# IntrepidDashboard.net
KiCad netlist of a schematic drawn in EAGLE
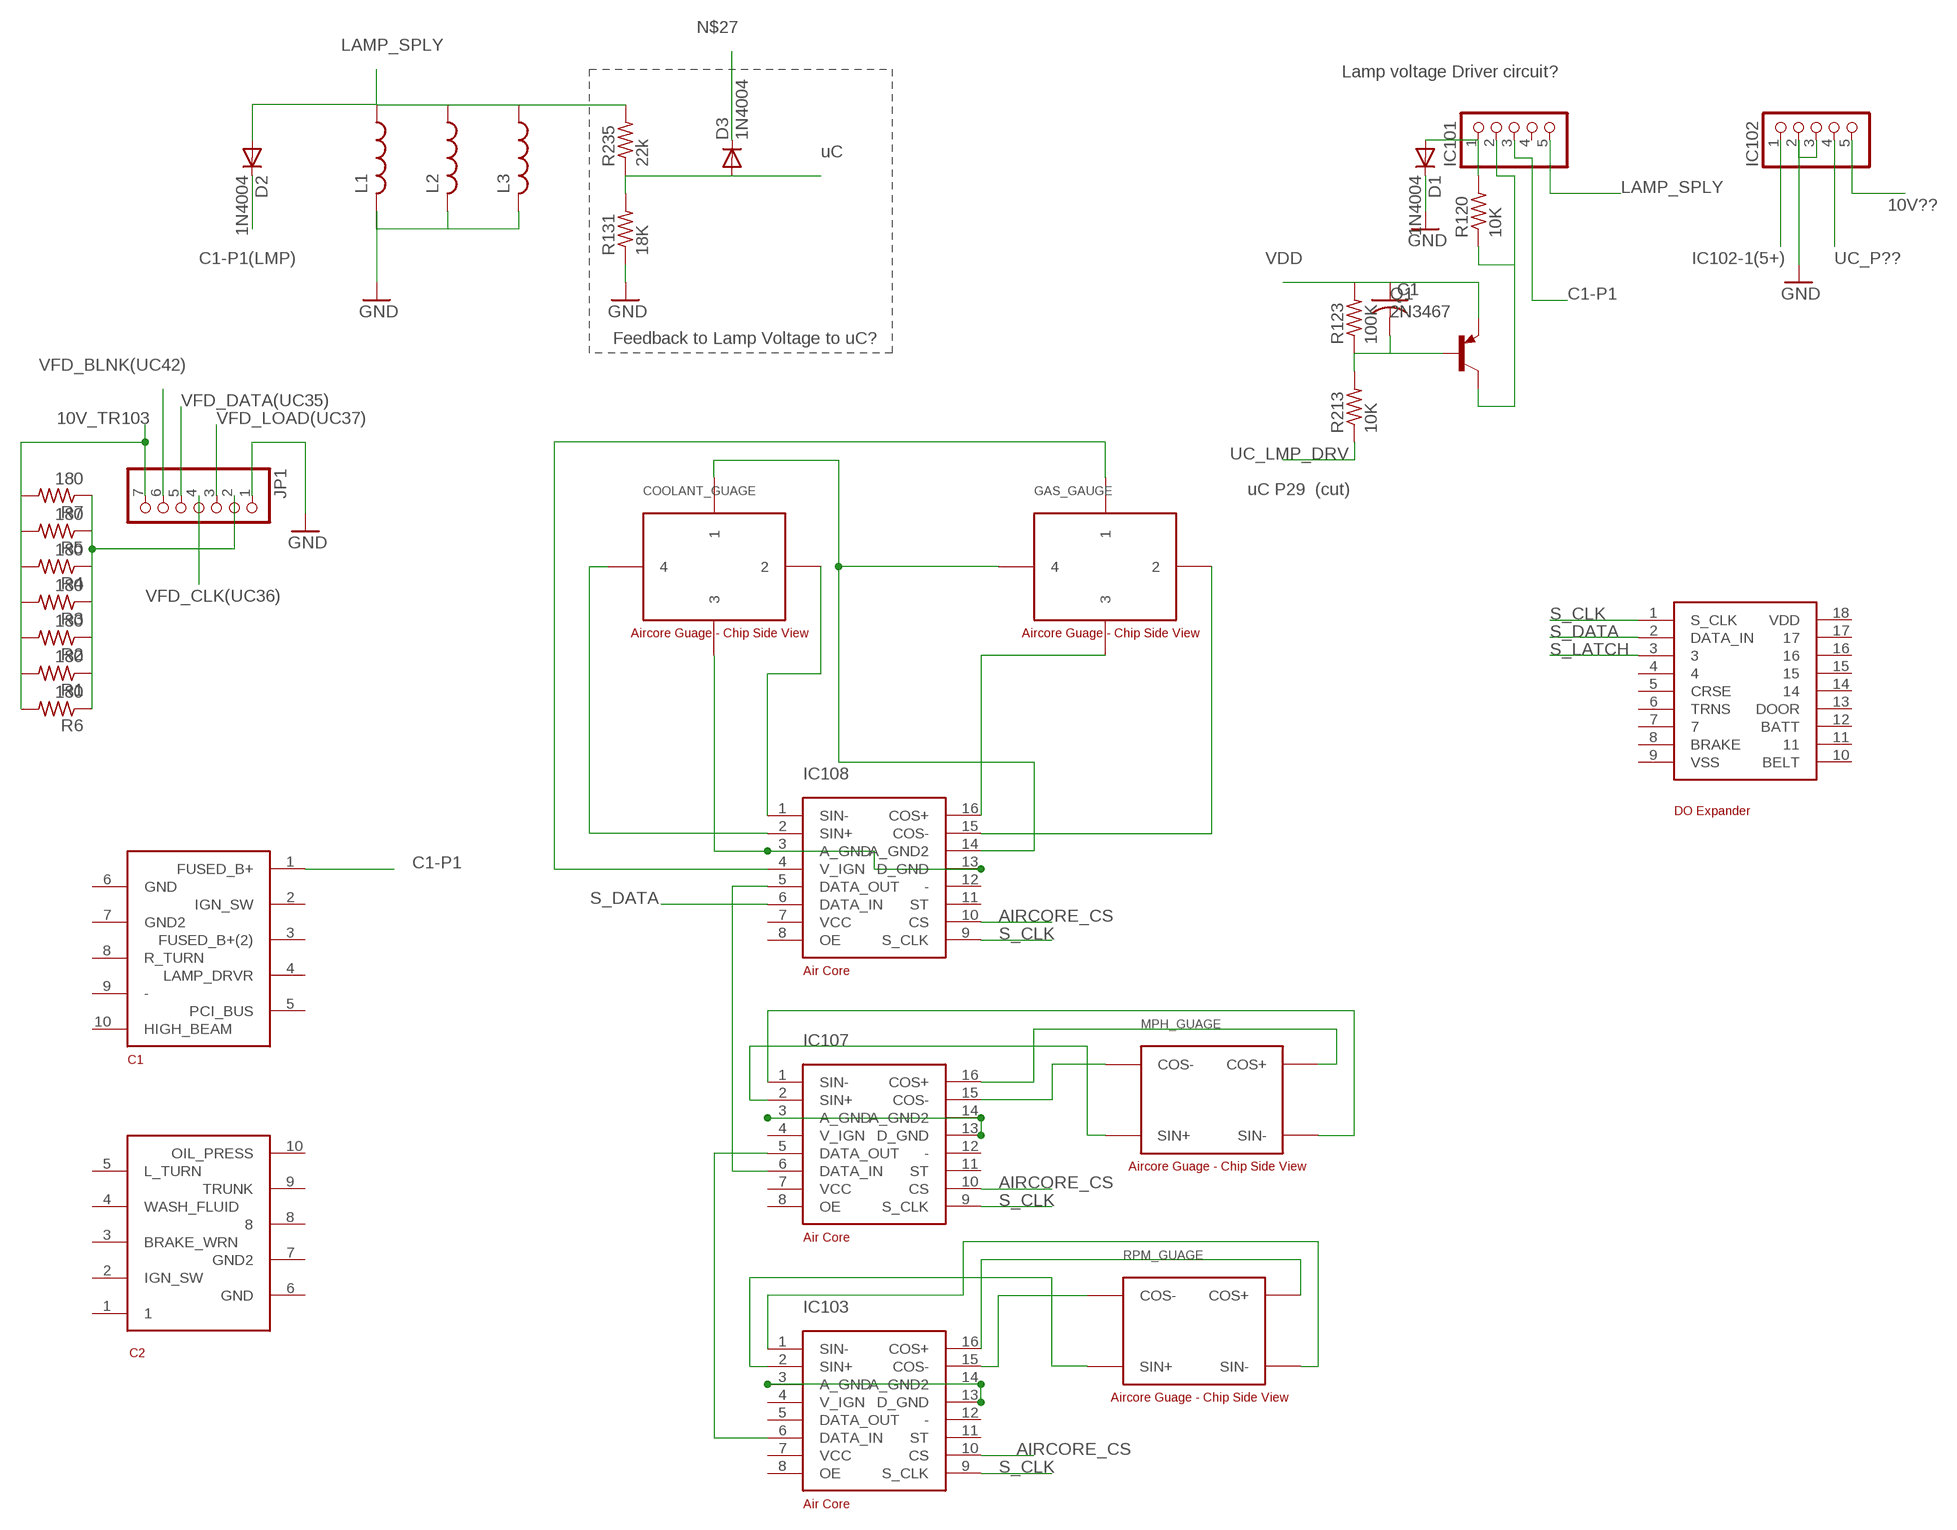
[diagram p0: schematic, sheet 1]

(export (version "E")
  (design (tool "Eeschema 10.0.6"))
  (components
    (comp (ref "C1")
      (value "C-US025-024X044")
      (footprint "eagle-import:C025-024X044")
      (libsource (lib "eagle-import") (part "C-US025-024X044"))
    )
    (comp (ref "COOLANT_GUAGE")
      (value "AIRCORE_GAUGE1")
      (footprint "eagle-import:AIRCORE1")
      (libsource (lib "eagle-import") (part "AIRCORE_GAUGE1"))
    )
    (comp (ref "D1")
      (value "1N4004")
      (footprint "eagle-import:DO41-10")
      (libsource (lib "eagle-import") (part "1N4004"))
    )
    (comp (ref "D2")
      (value "1N4004")
      (footprint "eagle-import:DO41-10")
      (libsource (lib "eagle-import") (part "1N4004"))
    )
    (comp (ref "D3")
      (value "1N4004")
      (footprint "eagle-import:DO41-10")
      (libsource (lib "eagle-import") (part "1N4004"))
    )
    (comp (ref "GAS_GAUGE")
      (value "AIRCORE_GAUGE1")
      (footprint "eagle-import:AIRCORE1")
      (libsource (lib "eagle-import") (part "AIRCORE_GAUGE1"))
    )
    (comp (ref "IC101")
      (value "PINHD-1X5")
      (footprint "eagle-import:1X05")
      (libsource (lib "eagle-import") (part "PINHD-1X5"))
    )
    (comp (ref "IC102")
      (value "PINHD-1X5")
      (footprint "eagle-import:1X05")
      (libsource (lib "eagle-import") (part "PINHD-1X5"))
    )
    (comp (ref "IC103")
      (value "AIR_CORE")
      (footprint "eagle-import:SOIC-16")
      (libsource (lib "eagle-import") (part "AIR_CORE"))
    )
    (comp (ref "IC107")
      (value "AIR_CORE")
      (footprint "eagle-import:SOIC-16")
      (libsource (lib "eagle-import") (part "AIR_CORE"))
    )
    (comp (ref "IC108")
      (value "AIR_CORE")
      (footprint "eagle-import:SOIC-16")
      (libsource (lib "eagle-import") (part "AIR_CORE"))
    )
    (comp (ref "JP1")
      (value "PINHD-1X7")
      (footprint "eagle-import:1X07")
      (libsource (lib "eagle-import") (part "PINHD-1X7"))
    )
    (comp (ref "L1")
      (value "L-US0204/5")
      (footprint "eagle-import:0204_5")
      (libsource (lib "eagle-import") (part "L-US0204/5"))
    )
    (comp (ref "L2")
      (value "L-US0204/5")
      (footprint "eagle-import:0204_5")
      (libsource (lib "eagle-import") (part "L-US0204/5"))
    )
    (comp (ref "L3")
      (value "L-US0204/5")
      (footprint "eagle-import:0204_5")
      (libsource (lib "eagle-import") (part "L-US0204/5"))
    )
    (comp (ref "MPH_GUAGE")
      (value "AIRCORE_GUAGE2")
      (footprint "eagle-import:AIRCORE1")
      (libsource (lib "eagle-import") (part "AIRCORE_GUAGE2"))
    )
    (comp (ref "Q1")
      (value "2N3467")
      (footprint "eagle-import:TO39")
      (libsource (lib "eagle-import") (part "2N3467"))
    )
    (comp (ref "R1")
      (value "180")
      (footprint "eagle-import:0204V")
      (libsource (lib "eagle-import") (part "R-US_0204/2V"))
    )
    (comp (ref "R2")
      (value "180")
      (footprint "eagle-import:0204V")
      (libsource (lib "eagle-import") (part "R-US_0204/2V"))
    )
    (comp (ref "R3")
      (value "180")
      (footprint "eagle-import:0204V")
      (libsource (lib "eagle-import") (part "R-US_0204/2V"))
    )
    (comp (ref "R4")
      (value "180")
      (footprint "eagle-import:0204V")
      (libsource (lib "eagle-import") (part "R-US_0204/2V"))
    )
    (comp (ref "R5")
      (value "180")
      (footprint "eagle-import:0204V")
      (libsource (lib "eagle-import") (part "R-US_0204/2V"))
    )
    (comp (ref "R6")
      (value "180")
      (footprint "eagle-import:0204V")
      (libsource (lib "eagle-import") (part "R-US_0204/2V"))
    )
    (comp (ref "R7")
      (value "180")
      (footprint "eagle-import:0204V")
      (libsource (lib "eagle-import") (part "R-US_0204/2V"))
    )
    (comp (ref "R120")
      (value "10K")
      (footprint "eagle-import:0204V")
      (libsource (lib "eagle-import") (part "R-US_0204/2V"))
    )
    (comp (ref "R123")
      (value "100K")
      (footprint "eagle-import:0204V")
      (libsource (lib "eagle-import") (part "R-US_0204/2V"))
    )
    (comp (ref "R131")
      (value "18K")
      (footprint "eagle-import:0204V")
      (libsource (lib "eagle-import") (part "R-US_0204/2V"))
    )
    (comp (ref "R213")
      (value "10K")
      (footprint "eagle-import:0204V")
      (libsource (lib "eagle-import") (part "R-US_0204/2V"))
    )
    (comp (ref "R235")
      (value "22k")
      (footprint "eagle-import:0204V")
      (libsource (lib "eagle-import") (part "R-US_0204/2V"))
    )
    (comp (ref "RPM_GUAGE")
      (value "AIRCORE_GUAGE2")
      (footprint "eagle-import:AIRCORE1")
      (libsource (lib "eagle-import") (part "AIRCORE_GUAGE2"))
    )
    (comp (ref "U$1")
      (value "DO_EXPANDER")
      (footprint "eagle-import:SOIC-18")
      (libsource (lib "eagle-import") (part "DO_EXPANDER"))
    )
    (comp (ref "U$2")
      (value "C1")
      (footprint "eagle-import:UMAX_10")
      (libsource (lib "eagle-import") (part "C1"))
    )
    (comp (ref "U$3")
      (value "C2")
      (footprint "eagle-import:UMAX_10")
      (libsource (lib "eagle-import") (part "C2"))
    )
  )
  (nets
    (net (code "1") (name "/10V??") (class "Default")
      (node (ref "IC102") (pin "5") (pinfunction "5_5") (pintype "passive"))
    )
    (net (code "2") (name "/10V_TR103") (class "Default")
      (node (ref "JP1") (pin "7") (pinfunction "7_7") (pintype "passive"))
      (node (ref "R1") (pin "2") (pinfunction "2_2") (pintype "passive"))
      (node (ref "R2") (pin "2") (pinfunction "2_2") (pintype "passive"))
      (node (ref "R3") (pin "2") (pinfunction "2_2") (pintype "passive"))
      (node (ref "R4") (pin "2") (pinfunction "2_2") (pintype "passive"))
      (node (ref "R5") (pin "2") (pinfunction "2_2") (pintype "passive"))
      (node (ref "R6") (pin "2") (pinfunction "2_2") (pintype "passive"))
      (node (ref "R7") (pin "2") (pinfunction "2_2") (pintype "passive"))
    )
    (net (code "3") (name "/AIRCORE_CS") (class "Default")
      (node (ref "IC103") (pin "10") (pinfunction "CS_10") (pintype "bidirectional"))
      (node (ref "IC107") (pin "10") (pinfunction "CS_10") (pintype "bidirectional"))
      (node (ref "IC108") (pin "10") (pinfunction "CS_10") (pintype "bidirectional"))
    )
    (net (code "4") (name "/C1-P1") (class "Default")
      (node (ref "IC101") (pin "3") (pinfunction "3_3") (pintype "passive"))
      (node (ref "U$2") (pin "1") (pinfunction "FUSED_B+_1") (pintype "bidirectional"))
    )
    (net (code "5") (name "/C1-P1(LMP)") (class "Default")
      (node (ref "D2") (pin "C") (pinfunction "C_C") (pintype "passive"))
    )
    (net (code "6") (name "/IC102-1(5+)") (class "Default")
      (node (ref "IC102") (pin "1") (pinfunction "1_1") (pintype "passive"))
    )
    (net (code "7") (name "/LAMP_SPLY") (class "Default")
      (node (ref "D2") (pin "A") (pinfunction "A_A") (pintype "passive"))
      (node (ref "IC101") (pin "5") (pinfunction "5_5") (pintype "passive"))
      (node (ref "L1") (pin "1") (pinfunction "1_1") (pintype "passive"))
      (node (ref "L2") (pin "1") (pinfunction "1_1") (pintype "passive"))
      (node (ref "L3") (pin "1") (pinfunction "1_1") (pintype "passive"))
      (node (ref "R235") (pin "2") (pinfunction "2_2") (pintype "passive"))
    )
    (net (code "8") (name "/N$27") (class "Default")
      (node (ref "D3") (pin "C") (pinfunction "C_C") (pintype "passive"))
    )
    (net (code "9") (name "/S_CLK") (class "Default")
      (node (ref "IC103") (pin "9") (pinfunction "S_CLK_9") (pintype "bidirectional"))
      (node (ref "IC107") (pin "9") (pinfunction "S_CLK_9") (pintype "bidirectional"))
      (node (ref "IC108") (pin "9") (pinfunction "S_CLK_9") (pintype "bidirectional"))
      (node (ref "U$1") (pin "1") (pinfunction "S_CLK_1") (pintype "bidirectional"))
    )
    (net (code "10") (name "/S_DATA") (class "Default")
      (node (ref "IC108") (pin "6") (pinfunction "DATA_IN_6") (pintype "bidirectional"))
      (node (ref "U$1") (pin "2") (pinfunction "DATA_IN_2") (pintype "bidirectional"))
    )
    (net (code "11") (name "/S_LATCH") (class "Default")
      (node (ref "U$1") (pin "3") (pinfunction "3_3") (pintype "bidirectional"))
    )
    (net (code "12") (name "/UC_LMP_DRV") (class "Default")
      (node (ref "R213") (pin "1") (pinfunction "1_1") (pintype "passive"))
    )
    (net (code "13") (name "/UC_P??") (class "Default")
      (node (ref "IC102") (pin "4") (pinfunction "4_4") (pintype "passive"))
    )
    (net (code "14") (name "/VDD") (class "Default")
      (node (ref "C1") (pin "1") (pinfunction "1_1") (pintype "passive"))
      (node (ref "Q1") (pin "1") (pinfunction "E_1") (pintype "passive"))
      (node (ref "R123") (pin "2") (pinfunction "2_2") (pintype "passive"))
    )
    (net (code "15") (name "/VFD_BLNK(UC42)") (class "Default")
      (node (ref "JP1") (pin "6") (pinfunction "6_6") (pintype "passive"))
    )
    (net (code "16") (name "/VFD_CLK(UC36)") (class "Default")
      (node (ref "JP1") (pin "4") (pinfunction "4_4") (pintype "passive"))
    )
    (net (code "17") (name "/VFD_DATA(UC35)") (class "Default")
      (node (ref "JP1") (pin "5") (pinfunction "5_5") (pintype "passive"))
    )
    (net (code "18") (name "/VFD_LOAD(UC37)") (class "Default")
      (node (ref "JP1") (pin "3") (pinfunction "3_3") (pintype "passive"))
    )
    (net (code "19") (name "GND") (class "Default")
      (node (ref "D1") (pin "C") (pinfunction "C_C") (pintype "passive"))
      (node (ref "IC102") (pin "2") (pinfunction "2_2") (pintype "passive"))
      (node (ref "IC102") (pin "3") (pinfunction "3_3") (pintype "passive"))
      (node (ref "JP1") (pin "1") (pinfunction "1_1") (pintype "passive"))
      (node (ref "L1") (pin "2") (pinfunction "2_2") (pintype "passive"))
      (node (ref "L2") (pin "2") (pinfunction "2_2") (pintype "passive"))
      (node (ref "L3") (pin "2") (pinfunction "2_2") (pintype "passive"))
      (node (ref "R131") (pin "1") (pinfunction "1_1") (pintype "passive"))
    )
    (net (code "20") (name "Net-(COOLANT_GUAGE-1)") (class "Default")
      (node (ref "COOLANT_GUAGE") (pin "P$1") (pinfunction "1_P$1") (pintype "bidirectional"))
      (node (ref "GAS_GAUGE") (pin "P$4") (pinfunction "4_P$4") (pintype "bidirectional"))
      (node (ref "IC108") (pin "14") (pinfunction "A_GND2_14") (pintype "bidirectional"))
    )
    (net (code "21") (name "Net-(COOLANT_GUAGE-2)") (class "Default")
      (node (ref "COOLANT_GUAGE") (pin "P$2") (pinfunction "2_P$2") (pintype "bidirectional"))
      (node (ref "IC108") (pin "1") (pinfunction "SIN-_1") (pintype "bidirectional"))
    )
    (net (code "22") (name "Net-(COOLANT_GUAGE-3)") (class "Default")
      (node (ref "COOLANT_GUAGE") (pin "P$3") (pinfunction "3_P$3") (pintype "bidirectional"))
      (node (ref "IC108") (pin "13") (pinfunction "D_GND_13") (pintype "bidirectional"))
      (node (ref "IC108") (pin "3") (pinfunction "A_GND_3") (pintype "bidirectional"))
    )
    (net (code "23") (name "Net-(COOLANT_GUAGE-4)") (class "Default")
      (node (ref "COOLANT_GUAGE") (pin "P$4") (pinfunction "4_P$4") (pintype "bidirectional"))
      (node (ref "IC108") (pin "2") (pinfunction "SIN+_2") (pintype "bidirectional"))
    )
    (net (code "24") (name "Net-(D1-PadA)") (class "Default")
      (node (ref "D1") (pin "A") (pinfunction "A_A") (pintype "passive"))
      (node (ref "IC101") (pin "1") (pinfunction "1_1") (pintype "passive"))
      (node (ref "R120") (pin "2") (pinfunction "2_2") (pintype "passive"))
    )
    (net (code "25") (name "Net-(D3-PadA)") (class "Default")
      (node (ref "D3") (pin "A") (pinfunction "A_A") (pintype "passive"))
      (node (ref "R131") (pin "2") (pinfunction "2_2") (pintype "passive"))
      (node (ref "R235") (pin "1") (pinfunction "1_1") (pintype "passive"))
    )
    (net (code "26") (name "Net-(GAS_GAUGE-1)") (class "Default")
      (node (ref "GAS_GAUGE") (pin "P$1") (pinfunction "1_P$1") (pintype "bidirectional"))
      (node (ref "IC108") (pin "4") (pinfunction "V_IGN_4") (pintype "bidirectional"))
    )
    (net (code "27") (name "Net-(GAS_GAUGE-2)") (class "Default")
      (node (ref "GAS_GAUGE") (pin "P$2") (pinfunction "2_P$2") (pintype "bidirectional"))
      (node (ref "IC108") (pin "15") (pinfunction "COS-_15") (pintype "bidirectional"))
    )
    (net (code "28") (name "Net-(GAS_GAUGE-3)") (class "Default")
      (node (ref "GAS_GAUGE") (pin "P$3") (pinfunction "3_P$3") (pintype "bidirectional"))
      (node (ref "IC108") (pin "16") (pinfunction "COS+_16") (pintype "bidirectional"))
    )
    (net (code "29") (name "Net-(IC103-A_GND)") (class "Default")
      (node (ref "IC103") (pin "13") (pinfunction "D_GND_13") (pintype "bidirectional"))
      (node (ref "IC103") (pin "14") (pinfunction "A_GND2_14") (pintype "bidirectional"))
      (node (ref "IC103") (pin "3") (pinfunction "A_GND_3") (pintype "bidirectional"))
    )
    (net (code "30") (name "Net-(IC103-COS+)") (class "Default")
      (node (ref "IC103") (pin "16") (pinfunction "COS+_16") (pintype "bidirectional"))
      (node (ref "RPM_GUAGE") (pin "P$1") (pinfunction "COS+_P$1") (pintype "bidirectional"))
    )
    (net (code "31") (name "Net-(IC103-COS-)") (class "Default")
      (node (ref "IC103") (pin "15") (pinfunction "COS-_15") (pintype "bidirectional"))
      (node (ref "RPM_GUAGE") (pin "P$2") (pinfunction "COS-_P$2") (pintype "bidirectional"))
    )
    (net (code "32") (name "Net-(IC103-DATA_IN)") (class "Default")
      (node (ref "IC103") (pin "6") (pinfunction "DATA_IN_6") (pintype "bidirectional"))
      (node (ref "IC107") (pin "5") (pinfunction "DATA_OUT_5") (pintype "bidirectional"))
    )
    (net (code "33") (name "Net-(IC103-SIN+)") (class "Default")
      (node (ref "IC103") (pin "2") (pinfunction "SIN+_2") (pintype "bidirectional"))
      (node (ref "RPM_GUAGE") (pin "P$3") (pinfunction "SIN+_P$3") (pintype "bidirectional"))
    )
    (net (code "34") (name "Net-(IC103-SIN-)") (class "Default")
      (node (ref "IC103") (pin "1") (pinfunction "SIN-_1") (pintype "bidirectional"))
      (node (ref "RPM_GUAGE") (pin "P$4") (pinfunction "SIN-_P$4") (pintype "bidirectional"))
    )
    (net (code "35") (name "Net-(IC107-A_GND)") (class "Default")
      (node (ref "IC107") (pin "13") (pinfunction "D_GND_13") (pintype "bidirectional"))
      (node (ref "IC107") (pin "14") (pinfunction "A_GND2_14") (pintype "bidirectional"))
      (node (ref "IC107") (pin "3") (pinfunction "A_GND_3") (pintype "bidirectional"))
    )
    (net (code "36") (name "Net-(IC107-COS+)") (class "Default")
      (node (ref "IC107") (pin "16") (pinfunction "COS+_16") (pintype "bidirectional"))
      (node (ref "MPH_GUAGE") (pin "P$1") (pinfunction "COS+_P$1") (pintype "bidirectional"))
    )
    (net (code "37") (name "Net-(IC107-COS-)") (class "Default")
      (node (ref "IC107") (pin "15") (pinfunction "COS-_15") (pintype "bidirectional"))
      (node (ref "MPH_GUAGE") (pin "P$2") (pinfunction "COS-_P$2") (pintype "bidirectional"))
    )
    (net (code "38") (name "Net-(IC107-DATA_IN)") (class "Default")
      (node (ref "IC107") (pin "6") (pinfunction "DATA_IN_6") (pintype "bidirectional"))
      (node (ref "IC108") (pin "5") (pinfunction "DATA_OUT_5") (pintype "bidirectional"))
    )
    (net (code "39") (name "Net-(IC107-SIN+)") (class "Default")
      (node (ref "IC107") (pin "2") (pinfunction "SIN+_2") (pintype "bidirectional"))
      (node (ref "MPH_GUAGE") (pin "P$3") (pinfunction "SIN+_P$3") (pintype "bidirectional"))
    )
    (net (code "40") (name "Net-(IC107-SIN-)") (class "Default")
      (node (ref "IC107") (pin "1") (pinfunction "SIN-_1") (pintype "bidirectional"))
      (node (ref "MPH_GUAGE") (pin "P$4") (pinfunction "SIN-_P$4") (pintype "bidirectional"))
    )
    (net (code "41") (name "Net-(JP1-Pad2)") (class "Default")
      (node (ref "JP1") (pin "2") (pinfunction "2_2") (pintype "passive"))
      (node (ref "R1") (pin "1") (pinfunction "1_1") (pintype "passive"))
      (node (ref "R2") (pin "1") (pinfunction "1_1") (pintype "passive"))
      (node (ref "R3") (pin "1") (pinfunction "1_1") (pintype "passive"))
      (node (ref "R4") (pin "1") (pinfunction "1_1") (pintype "passive"))
      (node (ref "R5") (pin "1") (pinfunction "1_1") (pintype "passive"))
      (node (ref "R6") (pin "1") (pinfunction "1_1") (pintype "passive"))
      (node (ref "R7") (pin "1") (pinfunction "1_1") (pintype "passive"))
    )
    (net (code "42") (name "Net-(Q1-B)") (class "Default")
      (node (ref "C1") (pin "2") (pinfunction "2_2") (pintype "passive"))
      (node (ref "Q1") (pin "2") (pinfunction "B_2") (pintype "passive"))
      (node (ref "R123") (pin "1") (pinfunction "1_1") (pintype "passive"))
      (node (ref "R213") (pin "2") (pinfunction "2_2") (pintype "passive"))
    )
    (net (code "43") (name "Net-(Q1-C)") (class "Default")
      (node (ref "IC101") (pin "2") (pinfunction "2_2") (pintype "passive"))
      (node (ref "Q1") (pin "3") (pinfunction "C_3") (pintype "passive"))
      (node (ref "R120") (pin "1") (pinfunction "1_1") (pintype "passive"))
    )
    (net (code "44") (name "unconnected-(IC101-Pad4)") (class "Default")
      (node (ref "IC101") (pin "4") (pinfunction "4_4") (pintype "passive"))
    )
    (net (code "45") (name "unconnected-(IC103---Pad12)") (class "Default")
      (node (ref "IC103") (pin "12") (pinfunction "-_12") (pintype "bidirectional"))
    )
    (net (code "46") (name "unconnected-(IC103-DATA_OUT-Pad5)") (class "Default")
      (node (ref "IC103") (pin "5") (pinfunction "DATA_OUT_5") (pintype "bidirectional"))
    )
    (net (code "47") (name "unconnected-(IC103-OE-Pad8)") (class "Default")
      (node (ref "IC103") (pin "8") (pinfunction "OE_8") (pintype "bidirectional"))
    )
    (net (code "48") (name "unconnected-(IC103-ST-Pad11)") (class "Default")
      (node (ref "IC103") (pin "11") (pinfunction "ST_11") (pintype "bidirectional"))
    )
    (net (code "49") (name "unconnected-(IC103-VCC-Pad7)") (class "Default")
      (node (ref "IC103") (pin "7") (pinfunction "VCC_7") (pintype "bidirectional"))
    )
    (net (code "50") (name "unconnected-(IC103-V_IGN-Pad4)") (class "Default")
      (node (ref "IC103") (pin "4") (pinfunction "V_IGN_4") (pintype "bidirectional"))
    )
    (net (code "51") (name "unconnected-(IC107---Pad12)") (class "Default")
      (node (ref "IC107") (pin "12") (pinfunction "-_12") (pintype "bidirectional"))
    )
    (net (code "52") (name "unconnected-(IC107-OE-Pad8)") (class "Default")
      (node (ref "IC107") (pin "8") (pinfunction "OE_8") (pintype "bidirectional"))
    )
    (net (code "53") (name "unconnected-(IC107-ST-Pad11)") (class "Default")
      (node (ref "IC107") (pin "11") (pinfunction "ST_11") (pintype "bidirectional"))
    )
    (net (code "54") (name "unconnected-(IC107-VCC-Pad7)") (class "Default")
      (node (ref "IC107") (pin "7") (pinfunction "VCC_7") (pintype "bidirectional"))
    )
    (net (code "55") (name "unconnected-(IC107-V_IGN-Pad4)") (class "Default")
      (node (ref "IC107") (pin "4") (pinfunction "V_IGN_4") (pintype "bidirectional"))
    )
    (net (code "56") (name "unconnected-(IC108---Pad12)") (class "Default")
      (node (ref "IC108") (pin "12") (pinfunction "-_12") (pintype "bidirectional"))
    )
    (net (code "57") (name "unconnected-(IC108-OE-Pad8)") (class "Default")
      (node (ref "IC108") (pin "8") (pinfunction "OE_8") (pintype "bidirectional"))
    )
    (net (code "58") (name "unconnected-(IC108-ST-Pad11)") (class "Default")
      (node (ref "IC108") (pin "11") (pinfunction "ST_11") (pintype "bidirectional"))
    )
    (net (code "59") (name "unconnected-(IC108-VCC-Pad7)") (class "Default")
      (node (ref "IC108") (pin "7") (pinfunction "VCC_7") (pintype "bidirectional"))
    )
    (net (code "60") (name "unconnected-(U$1-BATT-Pad12)") (class "Default")
      (node (ref "U$1") (pin "12") (pinfunction "BATT_12") (pintype "bidirectional"))
    )
    (net (code "61") (name "unconnected-(U$1-BELT-Pad10)") (class "Default")
      (node (ref "U$1") (pin "10") (pinfunction "BELT_10") (pintype "bidirectional"))
    )
    (net (code "62") (name "unconnected-(U$1-BRAKE-Pad8)") (class "Default")
      (node (ref "U$1") (pin "8") (pinfunction "BRAKE_8") (pintype "bidirectional"))
    )
    (net (code "63") (name "unconnected-(U$1-CRSE-Pad5)") (class "Default")
      (node (ref "U$1") (pin "5") (pinfunction "CRSE_5") (pintype "bidirectional"))
    )
    (net (code "64") (name "unconnected-(U$1-DOOR-Pad13)") (class "Default")
      (node (ref "U$1") (pin "13") (pinfunction "DOOR_13") (pintype "bidirectional"))
    )
    (net (code "65") (name "unconnected-(U$1-Pad4)") (class "Default")
      (node (ref "U$1") (pin "4") (pinfunction "4_4") (pintype "bidirectional"))
    )
    (net (code "66") (name "unconnected-(U$1-Pad7)") (class "Default")
      (node (ref "U$1") (pin "7") (pinfunction "7_7") (pintype "bidirectional"))
    )
    (net (code "67") (name "unconnected-(U$1-Pad11)") (class "Default")
      (node (ref "U$1") (pin "11") (pinfunction "11_11") (pintype "bidirectional"))
    )
    (net (code "68") (name "unconnected-(U$1-Pad14)") (class "Default")
      (node (ref "U$1") (pin "14") (pinfunction "14_14") (pintype "bidirectional"))
    )
    (net (code "69") (name "unconnected-(U$1-Pad15)") (class "Default")
      (node (ref "U$1") (pin "15") (pinfunction "15_15") (pintype "bidirectional"))
    )
    (net (code "70") (name "unconnected-(U$1-Pad16)") (class "Default")
      (node (ref "U$1") (pin "16") (pinfunction "16_16") (pintype "bidirectional"))
    )
    (net (code "71") (name "unconnected-(U$1-Pad17)") (class "Default")
      (node (ref "U$1") (pin "17") (pinfunction "17_17") (pintype "bidirectional"))
    )
    (net (code "72") (name "unconnected-(U$1-TRNS-Pad6)") (class "Default")
      (node (ref "U$1") (pin "6") (pinfunction "TRNS_6") (pintype "bidirectional"))
    )
    (net (code "73") (name "unconnected-(U$1-VDD-Pad18)") (class "Default")
      (node (ref "U$1") (pin "18") (pinfunction "VDD_18") (pintype "bidirectional"))
    )
    (net (code "74") (name "unconnected-(U$1-VSS-Pad9)") (class "Default")
      (node (ref "U$1") (pin "9") (pinfunction "VSS_9") (pintype "bidirectional"))
    )
    (net (code "75") (name "unconnected-(U$2---Pad9)") (class "Default")
      (node (ref "U$2") (pin "9") (pinfunction "-_9") (pintype "bidirectional"))
    )
    (net (code "76") (name "unconnected-(U$2-FUSED_B+(2)-Pad3)") (class "Default")
      (node (ref "U$2") (pin "3") (pinfunction "FUSED_B+(2)_3") (pintype "bidirectional"))
    )
    (net (code "77") (name "unconnected-(U$2-GND-Pad6)") (class "Default")
      (node (ref "U$2") (pin "6") (pinfunction "GND_6") (pintype "bidirectional"))
    )
    (net (code "78") (name "unconnected-(U$2-GND2-Pad7)") (class "Default")
      (node (ref "U$2") (pin "7") (pinfunction "GND2_7") (pintype "bidirectional"))
    )
    (net (code "79") (name "unconnected-(U$2-HIGH_BEAM-Pad10)") (class "Default")
      (node (ref "U$2") (pin "10") (pinfunction "HIGH_BEAM_10") (pintype "bidirectional"))
    )
    (net (code "80") (name "unconnected-(U$2-IGN_SW-Pad2)") (class "Default")
      (node (ref "U$2") (pin "2") (pinfunction "IGN_SW_2") (pintype "bidirectional"))
    )
    (net (code "81") (name "unconnected-(U$2-LAMP_DRVR-Pad4)") (class "Default")
      (node (ref "U$2") (pin "4") (pinfunction "LAMP_DRVR_4") (pintype "bidirectional"))
    )
    (net (code "82") (name "unconnected-(U$2-PCI_BUS-Pad5)") (class "Default")
      (node (ref "U$2") (pin "5") (pinfunction "PCI_BUS_5") (pintype "bidirectional"))
    )
    (net (code "83") (name "unconnected-(U$2-R_TURN-Pad8)") (class "Default")
      (node (ref "U$2") (pin "8") (pinfunction "R_TURN_8") (pintype "bidirectional"))
    )
    (net (code "84") (name "unconnected-(U$3-BRAKE_WRN-Pad3)") (class "Default")
      (node (ref "U$3") (pin "3") (pinfunction "BRAKE_WRN_3") (pintype "bidirectional"))
    )
    (net (code "85") (name "unconnected-(U$3-GND-Pad6)") (class "Default")
      (node (ref "U$3") (pin "6") (pinfunction "GND_6") (pintype "bidirectional"))
    )
    (net (code "86") (name "unconnected-(U$3-GND2-Pad7)") (class "Default")
      (node (ref "U$3") (pin "7") (pinfunction "GND2_7") (pintype "bidirectional"))
    )
    (net (code "87") (name "unconnected-(U$3-IGN_SW-Pad2)") (class "Default")
      (node (ref "U$3") (pin "2") (pinfunction "IGN_SW_2") (pintype "bidirectional"))
    )
    (net (code "88") (name "unconnected-(U$3-L_TURN-Pad5)") (class "Default")
      (node (ref "U$3") (pin "5") (pinfunction "L_TURN_5") (pintype "bidirectional"))
    )
    (net (code "89") (name "unconnected-(U$3-OIL_PRESS-Pad10)") (class "Default")
      (node (ref "U$3") (pin "10") (pinfunction "OIL_PRESS_10") (pintype "bidirectional"))
    )
    (net (code "90") (name "unconnected-(U$3-Pad1)") (class "Default")
      (node (ref "U$3") (pin "1") (pinfunction "1_1") (pintype "bidirectional"))
    )
    (net (code "91") (name "unconnected-(U$3-Pad8)") (class "Default")
      (node (ref "U$3") (pin "8") (pinfunction "8_8") (pintype "bidirectional"))
    )
    (net (code "92") (name "unconnected-(U$3-TRUNK-Pad9)") (class "Default")
      (node (ref "U$3") (pin "9") (pinfunction "TRUNK_9") (pintype "bidirectional"))
    )
    (net (code "93") (name "unconnected-(U$3-WASH_FLUID-Pad4)") (class "Default")
      (node (ref "U$3") (pin "4") (pinfunction "WASH_FLUID_4") (pintype "bidirectional"))
    )
  )
)
